# ProPrj___2024-09-27.net
KiCad netlist of a schematic drawn in EasyEDA Pro
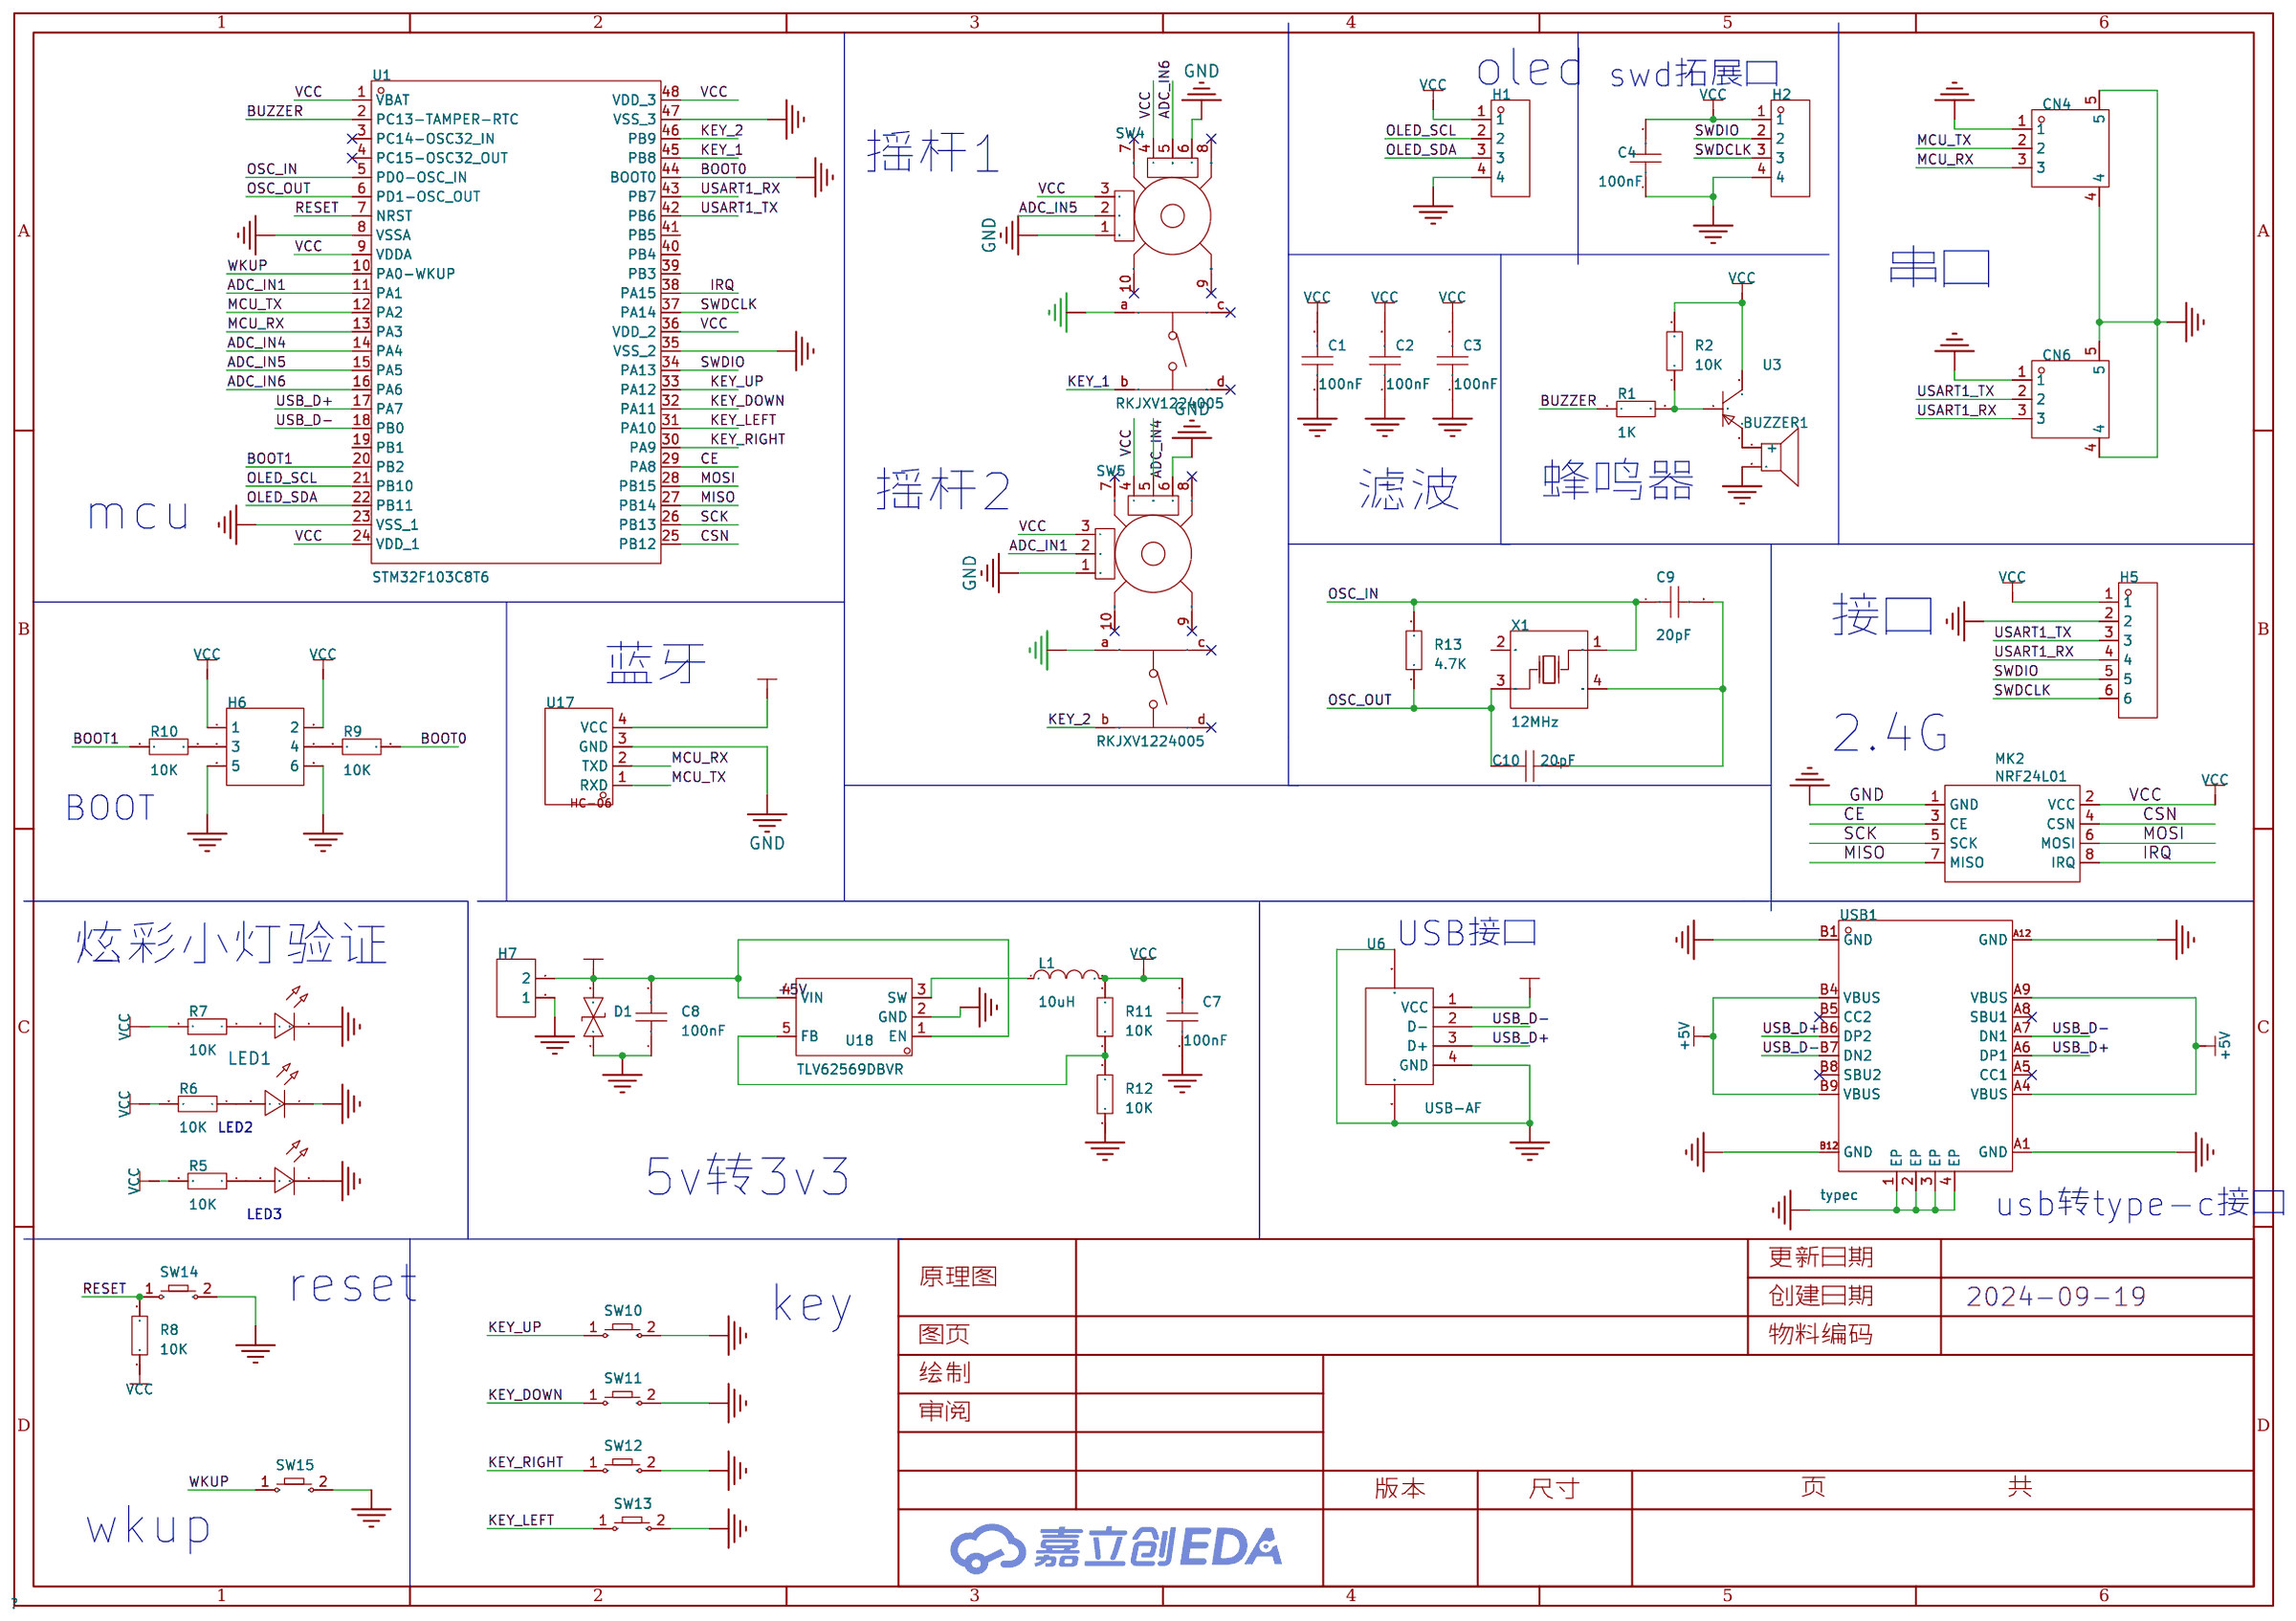
[diagram p0: schematic sheet]

(export (version "E")
  (design (tool "Eeschema 10.0.6"))
  (components
    (comp (ref "BUZZER1")
      (value "buzzer-12X9")
      (footprint "easyedapro:BUZ-TH_BD12.0-P7.60-D0.6-FD")
      (libsource (lib "easyedapro") (part "BUZZER-12X9"))
    )
    (comp (ref "C1")
      (value "100nF")
      (footprint "easyedapro:C0603")
      (libsource (lib "easyedapro") (part "CapAcitance"))
    )
    (comp (ref "C2")
      (value "100nF")
      (footprint "easyedapro:C0603")
      (libsource (lib "easyedapro") (part "CapAcitance"))
    )
    (comp (ref "C3")
      (value "100nF")
      (footprint "easyedapro:C0603")
      (libsource (lib "easyedapro") (part "CapAcitance"))
    )
    (comp (ref "C4")
      (value "100nF")
      (footprint "easyedapro:C0603")
      (libsource (lib "easyedapro") (part "CapAcitance"))
    )
    (comp (ref "C7")
      (value "100nF")
      (footprint "easyedapro:C0603")
      (libsource (lib "easyedapro") (part "CapAcitance"))
    )
    (comp (ref "C8")
      (value "100nF")
      (footprint "easyedapro:C0603")
      (libsource (lib "easyedapro") (part "CapAcitance"))
    )
    (comp (ref "C9")
      (value "20pF")
      (footprint "easyedapro:C0603")
      (libsource (lib "easyedapro") (part "CapAcitance"))
    )
    (comp (ref "C10")
      (value "20pF")
      (footprint "easyedapro:C0603")
      (libsource (lib "easyedapro") (part "CapAcitance"))
    )
    (comp (ref "CN4")
      (value "A1257WV-S-3P")
      (footprint "easyedapro:CONN-SMD_A1257WV-S-3P")
      (description "插针结构:1x3P;间距:1.25mm;安装方式:-;参考系列:GH;总PIN数:3P;排数:1;每排PIN数:3;行距:-;触头材质:黄铜;")
      (fields (field (name "Manufacturer") "CJT(长江连接器)"))
      (libsource (lib "easyedapro") (part "A1257WV-S-3P"))
    )
    (comp (ref "CN6")
      (value "A1257WV-S-3P")
      (footprint "easyedapro:CONN-SMD_A1257WV-S-3P")
      (description "插针结构:1x3P;间距:1.25mm;安装方式:-;参考系列:GH;总PIN数:3P;排数:1;每排PIN数:3;行距:-;触头材质:黄铜;")
      (fields (field (name "Manufacturer") "CJT(长江连接器)"))
      (libsource (lib "easyedapro") (part "A1257WV-S-3P"))
    )
    (comp (ref "D1")
      (value "P6SMB6.8CA/TR13")
      (footprint "easyedapro:SMB_L4.6-W3.6-LS5.3-BI")
      (description "反向截止电压(Vrwm):5.8V;最大钳位电压:10.5V;峰值脉冲电流(Ipp)@10/1000us:58.1A;峰值脉冲功率(Ppp)@10/1000us:600W;击穿电压:6.45V;")
      (fields (field (name "Manufacturer") "Brightking(君耀电子)"))
      (libsource (lib "easyedapro") (part "P6SMB6.8CA-C78395"))
    )
    (comp (ref "H1")
      (value "~")
      (footprint "easyedapro:HDR-TH_4P-P2.54-V-F")
      (libsource (lib "easyedapro") (part "2.54-1*4P母"))
    )
    (comp (ref "H2")
      (value "~")
      (footprint "easyedapro:HDR-TH_4P-P2.54-V-F")
      (libsource (lib "easyedapro") (part "2.54-1*4P母"))
    )
    (comp (ref "H5")
      (value "~")
      (footprint "easyedapro:HDR-TH_6P-P2.54-V-F")
      (libsource (lib "easyedapro") (part "Header-Female-2.54_1x6"))
    )
    (comp (ref "H6")
      (value "~")
      (footprint "easyedapro:HDR-TH_6P-P2.54-V-F-R2-C3-S2.54")
      (libsource (lib "easyedapro") (part "HDR-F-2.54_2x3"))
    )
    (comp (ref "H7")
      (value "~")
      (footprint "easyedapro:HDR-TH_2P-P2.54-V-F")
      (libsource (lib "easyedapro") (part "Header-Female-2.54_1x2"))
    )
    (comp (ref "L1")
      (value "10uH")
      (footprint "easyedapro:L0603")
      (libsource (lib "easyedapro") (part "SDFL1608S100KTF"))
    )
    (comp (ref "LED1")
      (value "~")
      (footprint "easyedapro:LED_0402")
      (libsource (lib "easyedapro") (part "LED_R"))
    )
    (comp (ref "LED2")
      (value "~")
      (footprint "easyedapro:LED_0603")
      (libsource (lib "easyedapro") (part "LED_G"))
    )
    (comp (ref "LED3")
      (value "~")
      (footprint "easyedapro:LED_0603")
      (libsource (lib "easyedapro") (part "LED_B"))
    )
    (comp (ref "MK2")
      (value "NRF24L01")
      (footprint "easyedapro:WIRELM-SMD_NRF24L01")
      (fields
        (field (name "Manufacturer Part") "NRF24L01+功率加强版绑定2.4Gwireless module")
        (field (name "Manufacturer") "Ai-Thinker")
      )
      (libsource (lib "easyedapro") (part "NRF24L01"))
    )
    (comp (ref "R1") (value "1K") (footprint "easyedapro:R0603") (libsource (lib "easyedapro") (part "电阻")))
    (comp (ref "R2") (value "10K") (footprint "easyedapro:R0603") (libsource (lib "easyedapro") (part "电阻")))
    (comp (ref "R5") (value "10K") (footprint "easyedapro:R0603") (libsource (lib "easyedapro") (part "电阻")))
    (comp (ref "R6") (value "10K") (footprint "easyedapro:R0603") (libsource (lib "easyedapro") (part "电阻")))
    (comp (ref "R7") (value "10K") (footprint "easyedapro:R0603") (libsource (lib "easyedapro") (part "电阻")))
    (comp (ref "R8") (value "10K") (footprint "easyedapro:R0603") (libsource (lib "easyedapro") (part "电阻")))
    (comp (ref "R9") (value "10K") (footprint "easyedapro:R0603") (libsource (lib "easyedapro") (part "电阻")))
    (comp (ref "R10") (value "10K") (footprint "easyedapro:R0603") (libsource (lib "easyedapro") (part "电阻")))
    (comp (ref "R11") (value "10K") (footprint "easyedapro:R0603") (libsource (lib "easyedapro") (part "电阻")))
    (comp (ref "R12") (value "10K") (footprint "easyedapro:R0603") (libsource (lib "easyedapro") (part "电阻")))
    (comp (ref "R13")
      (value "4.7K")
      (footprint "easyedapro:R0603")
      (libsource (lib "easyedapro") (part "电阻"))
    )
    (comp (ref "SW4")
      (value "RKJXV1224005")
      (footprint "easyedapro:SW-TH_RKJXV1224005")
      (description "操纵杆复位 中央按动开关 适用于航模玩具遥控器电位器、3D摇杆PS4手柄游戏机、无人机摇杆电位器、工业控制器")
      (fields (field (name "Manufacturer") "ALPSALPINE(阿尔卑斯阿尔派)"))
      (libsource (lib "easyedapro") (part "RKJXV1224005"))
    )
    (comp (ref "SW5")
      (value "RKJXV1224005")
      (footprint "easyedapro:SW-TH_RKJXV1224005")
      (description "操纵杆复位 中央按动开关 适用于航模玩具遥控器电位器、3D摇杆PS4手柄游戏机、无人机摇杆电位器、工业控制器")
      (fields (field (name "Manufacturer") "ALPSALPINE(阿尔卑斯阿尔派)"))
      (libsource (lib "easyedapro") (part "RKJXV1224005"))
    )
    (comp (ref "SW10")
      (value "~")
      (footprint "easyedapro:Key_SMD_3x4x2")
      (libsource (lib "easyedapro") (part "轻触按键x2"))
    )
    (comp (ref "SW11")
      (value "~")
      (footprint "easyedapro:Key_SMD_3x4x2")
      (libsource (lib "easyedapro") (part "轻触按键x2"))
    )
    (comp (ref "SW12")
      (value "~")
      (footprint "easyedapro:Key_SMD_3x4x2")
      (libsource (lib "easyedapro") (part "轻触按键x2"))
    )
    (comp (ref "SW13")
      (value "~")
      (footprint "easyedapro:Key_SMD_3x4x2")
      (libsource (lib "easyedapro") (part "轻触按键x2"))
    )
    (comp (ref "SW14")
      (value "~")
      (footprint "easyedapro:Key_SMD_3x4x2")
      (libsource (lib "easyedapro") (part "轻触按键x2"))
    )
    (comp (ref "SW15")
      (value "~")
      (footprint "easyedapro:Key_SMD_3x4x2")
      (libsource (lib "easyedapro") (part "轻触按键x2"))
    )
    (comp (ref "U1")
      (value "STM32F103C8T6")
      (footprint "easyedapro:LQFP-48_L7.0-W7.0-P0.50-LS9.0-BL")
      (description "CPU内核:ARM-M3;程序存储容量:64KB;RAM总容量:20KB;GPIO端口数量:37;工作电压范围:2V~3.6V;CPU最大主频:72MHz;程序存储器类型:FLASH;")
      (fields (field (name "Manufacturer") "ST(意法半导体)"))
      (libsource (lib "easyedapro") (part "STM32F103C8T6"))
    )
    (comp (ref "U3")
      (value "S9012")
      (footprint "easyedapro:SOT-23-3_L2.9-W1.3-P0.95-LS2.4-BR")
      (fields (field (name "Manufacturer") "MSKSEMI(美森科)"))
      (libsource (lib "easyedapro") (part "S9012_C2914401"))
    )
    (comp (ref "U6")
      (value "USB-AF")
      (footprint "easyedapro:USB-A-TH_USB-302-T")
      (libsource (lib "easyedapro") (part "USB-AF"))
    )
    (comp (ref "U17")
      (value "~")
      (footprint "easyedapro:HC-06")
      (description "蓝牙模块-4P")
      (libsource (lib "easyedapro") (part "HC-06"))
    )
    (comp (ref "U18")
      (value "TLV62569DBVR")
      (footprint "easyedapro:SOT-23-5_L3.0-W1.7-P0.95-LS2.8-BR")
      (description "功能类型:降压型;输出类型:可调;输入电压:2.5V~5.5V;输出电压:600mV~5.5V;输出电流(最大值):2A;")
      (fields (field (name "Manufacturer") "TI(德州仪器)"))
      (libsource (lib "easyedapro") (part "TLV62569DBVR"))
    )
    (comp (ref "USB1")
      (value "typec")
      (footprint "easyedapro:USB-C-SMD_KH-TYPE-C-16P")
      (libsource (lib "easyedapro") (part "TYPEC_C9900016956"))
    )
    (comp (ref "X1")
      (value "12MHz")
      (footprint "easyedapro:OSC-SMD_4P-L3.2-W2.5-BL")
      (description "晶振类型:贴片晶振;频率:12MHz;常温频差:±10ppm;外接负载电容:20pF;频率稳定度(全温):±20ppm;")
      (fields (field (name "Manufacturer Part") "X322512MSB4SI") (field (name "Manufacturer") "YXC(扬兴晶振)"))
      (libsource (lib "easyedapro") (part "X322512MSB4SI"))
    )
  )
  (nets
    (net (code "1") (name "+5V") (class "Default")
      (node (ref "C8") (pin "2") (pinfunction "2_2") (pintype "input"))
      (node (ref "D1") (pin "2") (pinfunction "2_2") (pintype "unspecified"))
      (node (ref "H7") (pin "2") (pinfunction "2_2") (pintype "input"))
      (node (ref "U18") (pin "1") (pinfunction "EN_1") (pintype "unspecified"))
      (node (ref "U18") (pin "4") (pinfunction "VIN_4") (pintype "unspecified"))
      (node (ref "U6") (pin "1") (pinfunction "VCC_1") (pintype "unspecified"))
      (node (ref "USB1") (pin "A4") (pinfunction "VBUS_A4") (pintype "unspecified"))
      (node (ref "USB1") (pin "A9") (pinfunction "VBUS_A9") (pintype "unspecified"))
      (node (ref "USB1") (pin "B4") (pinfunction "VBUS_B4") (pintype "unspecified"))
      (node (ref "USB1") (pin "B9") (pinfunction "VBUS_B9") (pintype "unspecified"))
    )
    (net (code "2") (name "/ADC_IN1") (class "Default")
      (node (ref "SW5") (pin "2") (pinfunction "DTA_2") (pintype "input"))
      (node (ref "U1") (pin "11") (pinfunction "PA1_11") (pintype "unspecified"))
    )
    (net (code "3") (name "/ADC_IN4") (class "Default")
      (node (ref "SW5") (pin "5") (pinfunction "DTA_5") (pintype "input"))
      (node (ref "U1") (pin "14") (pinfunction "PA4_14") (pintype "unspecified"))
    )
    (net (code "4") (name "/ADC_IN5") (class "Default")
      (node (ref "SW4") (pin "2") (pinfunction "DTA_2") (pintype "input"))
      (node (ref "U1") (pin "15") (pinfunction "PA5_15") (pintype "unspecified"))
    )
    (net (code "5") (name "/ADC_IN6") (class "Default")
      (node (ref "SW4") (pin "5") (pinfunction "DTA_5") (pintype "input"))
      (node (ref "U1") (pin "16") (pinfunction "PA6_16") (pintype "unspecified"))
    )
    (net (code "6") (name "/BOOT1") (class "Default")
      (node (ref "R10") (pin "1") (pinfunction "1_1") (pintype "input"))
      (node (ref "U1") (pin "20") (pinfunction "PB2_20") (pintype "unspecified"))
    )
    (net (code "7") (name "/BUZZER") (class "Default")
      (node (ref "R1") (pin "1") (pinfunction "1_1") (pintype "input"))
      (node (ref "U1") (pin "2") (pinfunction "PC13-TAMPER-RTC_2") (pintype "unspecified"))
    )
    (net (code "8") (name "/CE") (class "Default")
      (node (ref "MK2") (pin "3") (pinfunction "CE_3") (pintype "unspecified"))
      (node (ref "U1") (pin "29") (pinfunction "PA8_29") (pintype "unspecified"))
    )
    (net (code "9") (name "/CSN") (class "Default")
      (node (ref "MK2") (pin "4") (pinfunction "CSN_4") (pintype "unspecified"))
      (node (ref "U1") (pin "25") (pinfunction "PB12_25") (pintype "unspecified"))
    )
    (net (code "10") (name "/IRQ") (class "Default")
      (node (ref "MK2") (pin "8") (pinfunction "IRQ_8") (pintype "unspecified"))
      (node (ref "U1") (pin "38") (pinfunction "PA15_38") (pintype "unspecified"))
    )
    (net (code "11") (name "/KEY_1") (class "Default")
      (node (ref "SW4") (pin "b") (pinfunction "b_b") (pintype "input"))
      (node (ref "U1") (pin "45") (pinfunction "PB8_45") (pintype "unspecified"))
    )
    (net (code "12") (name "/KEY_2") (class "Default")
      (node (ref "SW5") (pin "b") (pinfunction "b_b") (pintype "input"))
      (node (ref "U1") (pin "46") (pinfunction "PB9_46") (pintype "unspecified"))
    )
    (net (code "13") (name "/KEY_DOWN") (class "Default")
      (node (ref "SW11") (pin "1") (pinfunction "1_1") (pintype "input"))
      (node (ref "U1") (pin "32") (pinfunction "PA11_32") (pintype "unspecified"))
    )
    (net (code "14") (name "/KEY_LEFT") (class "Default")
      (node (ref "SW13") (pin "1") (pinfunction "1_1") (pintype "input"))
      (node (ref "U1") (pin "31") (pinfunction "PA10_31") (pintype "unspecified"))
    )
    (net (code "15") (name "/KEY_RIGHT") (class "Default")
      (node (ref "SW12") (pin "1") (pinfunction "1_1") (pintype "input"))
      (node (ref "U1") (pin "30") (pinfunction "PA9_30") (pintype "unspecified"))
    )
    (net (code "16") (name "/KEY_UP") (class "Default")
      (node (ref "SW10") (pin "1") (pinfunction "1_1") (pintype "input"))
      (node (ref "U1") (pin "33") (pinfunction "PA12_33") (pintype "unspecified"))
    )
    (net (code "17") (name "/MCU_RX") (class "Default")
      (node (ref "CN4") (pin "3") (pinfunction "3_3") (pintype "unspecified"))
      (node (ref "U1") (pin "13") (pinfunction "PA3_13") (pintype "unspecified"))
      (node (ref "U17") (pin "2") (pinfunction "TXD_2") (pintype "input"))
    )
    (net (code "18") (name "/MCU_TX") (class "Default")
      (node (ref "CN4") (pin "2") (pinfunction "2_2") (pintype "unspecified"))
      (node (ref "U1") (pin "12") (pinfunction "PA2_12") (pintype "unspecified"))
      (node (ref "U17") (pin "1") (pinfunction "RXD_1") (pintype "input"))
    )
    (net (code "19") (name "/MISO") (class "Default")
      (node (ref "MK2") (pin "7") (pinfunction "MISO_7") (pintype "unspecified"))
      (node (ref "U1") (pin "27") (pinfunction "PB14_27") (pintype "unspecified"))
    )
    (net (code "20") (name "/MOSI") (class "Default")
      (node (ref "MK2") (pin "6") (pinfunction "MOSI_6") (pintype "unspecified"))
      (node (ref "U1") (pin "28") (pinfunction "PB15_28") (pintype "unspecified"))
    )
    (net (code "21") (name "/OLED_SCL") (class "Default")
      (node (ref "H1") (pin "2") (pinfunction "2_2") (pintype "unspecified"))
      (node (ref "U1") (pin "21") (pinfunction "PB10_21") (pintype "unspecified"))
    )
    (net (code "22") (name "/OLED_SDA") (class "Default")
      (node (ref "H1") (pin "3") (pinfunction "3_3") (pintype "unspecified"))
      (node (ref "U1") (pin "22") (pinfunction "PB11_22") (pintype "unspecified"))
    )
    (net (code "23") (name "/OSC_IN") (class "Default")
      (node (ref "C9") (pin "1") (pinfunction "1_1") (pintype "input"))
      (node (ref "R13") (pin "2") (pinfunction "2_2") (pintype "input"))
      (node (ref "U1") (pin "5") (pinfunction "PD0-OSC_IN_5") (pintype "unspecified"))
      (node (ref "X1") (pin "1") (pinfunction "OSC1_1") (pintype "unspecified"))
    )
    (net (code "24") (name "/OSC_OUT") (class "Default")
      (node (ref "C10") (pin "1") (pinfunction "1_1") (pintype "input"))
      (node (ref "R13") (pin "1") (pinfunction "1_1") (pintype "input"))
      (node (ref "U1") (pin "6") (pinfunction "PD1-OSC_OUT_6") (pintype "unspecified"))
      (node (ref "X1") (pin "3") (pinfunction "OSC2_3") (pintype "unspecified"))
    )
    (net (code "25") (name "/RESET") (class "Default")
      (node (ref "R8") (pin "2") (pinfunction "2_2") (pintype "input"))
      (node (ref "SW14") (pin "1") (pinfunction "1_1") (pintype "input"))
      (node (ref "U1") (pin "7") (pinfunction "NRST_7") (pintype "unspecified"))
    )
    (net (code "26") (name "/SCK") (class "Default")
      (node (ref "MK2") (pin "5") (pinfunction "SCK_5") (pintype "unspecified"))
      (node (ref "U1") (pin "26") (pinfunction "PB13_26") (pintype "unspecified"))
    )
    (net (code "27") (name "/SWDCLK") (class "Default")
      (node (ref "H2") (pin "3") (pinfunction "3_3") (pintype "unspecified"))
      (node (ref "H5") (pin "6") (pinfunction "6_6") (pintype "unspecified"))
      (node (ref "U1") (pin "37") (pinfunction "PA14_37") (pintype "unspecified"))
    )
    (net (code "28") (name "/SWDIO") (class "Default")
      (node (ref "H2") (pin "2") (pinfunction "2_2") (pintype "unspecified"))
      (node (ref "H5") (pin "5") (pinfunction "5_5") (pintype "unspecified"))
      (node (ref "U1") (pin "34") (pinfunction "PA13_34") (pintype "unspecified"))
    )
    (net (code "29") (name "/USART1_RX") (class "Default")
      (node (ref "CN6") (pin "3") (pinfunction "3_3") (pintype "unspecified"))
      (node (ref "H5") (pin "4") (pinfunction "4_4") (pintype "unspecified"))
      (node (ref "U1") (pin "43") (pinfunction "PB7_43") (pintype "unspecified"))
    )
    (net (code "30") (name "/USART1_TX") (class "Default")
      (node (ref "CN6") (pin "2") (pinfunction "2_2") (pintype "unspecified"))
      (node (ref "H5") (pin "3") (pinfunction "3_3") (pintype "unspecified"))
      (node (ref "U1") (pin "42") (pinfunction "PB6_42") (pintype "unspecified"))
    )
    (net (code "31") (name "/USB_D+") (class "Default")
      (node (ref "U1") (pin "17") (pinfunction "PA7_17") (pintype "unspecified"))
      (node (ref "U6") (pin "3") (pinfunction "D+_3") (pintype "unspecified"))
      (node (ref "USB1") (pin "A6") (pinfunction "DP1_A6") (pintype "unspecified"))
      (node (ref "USB1") (pin "B6") (pinfunction "DP2_B6") (pintype "unspecified"))
    )
    (net (code "32") (name "/USB_D-") (class "Default")
      (node (ref "U1") (pin "18") (pinfunction "PB0_18") (pintype "unspecified"))
      (node (ref "U6") (pin "2") (pinfunction "D-_2") (pintype "unspecified"))
      (node (ref "USB1") (pin "A7") (pinfunction "DN1_A7") (pintype "unspecified"))
      (node (ref "USB1") (pin "B7") (pinfunction "DN2_B7") (pintype "unspecified"))
    )
    (net (code "33") (name "/WKUP") (class "Default")
      (node (ref "SW15") (pin "1") (pinfunction "1_1") (pintype "input"))
      (node (ref "U1") (pin "10") (pinfunction "PA0-WKUP_10") (pintype "unspecified"))
    )
    (net (code "34") (name "BOOT0") (class "Default")
      (node (ref "R9") (pin "2") (pinfunction "2_2") (pintype "input"))
      (node (ref "U1") (pin "44") (pinfunction "BOOT0_44") (pintype "unspecified"))
    )
    (net (code "35") (name "GND") (class "Default")
      (node (ref "BUZZER1") (pin "2") (pinfunction "2_2") (pintype "unspecified"))
      (node (ref "C1") (pin "1") (pinfunction "1_1") (pintype "input"))
      (node (ref "C2") (pin "1") (pinfunction "1_1") (pintype "input"))
      (node (ref "C3") (pin "1") (pinfunction "1_1") (pintype "input"))
      (node (ref "C4") (pin "1") (pinfunction "1_1") (pintype "input"))
      (node (ref "C7") (pin "1") (pinfunction "1_1") (pintype "input"))
      (node (ref "C8") (pin "1") (pinfunction "1_1") (pintype "input"))
      (node (ref "CN4") (pin "1") (pinfunction "1_1") (pintype "unspecified"))
      (node (ref "CN4") (pin "4") (pinfunction "4_4") (pintype "unspecified"))
      (node (ref "CN4") (pin "5") (pinfunction "5_5") (pintype "unspecified"))
      (node (ref "CN6") (pin "1") (pinfunction "1_1") (pintype "unspecified"))
      (node (ref "CN6") (pin "4") (pinfunction "4_4") (pintype "unspecified"))
      (node (ref "CN6") (pin "5") (pinfunction "5_5") (pintype "unspecified"))
      (node (ref "D1") (pin "1") (pinfunction "1_1") (pintype "unspecified"))
      (node (ref "H1") (pin "4") (pinfunction "4_4") (pintype "unspecified"))
      (node (ref "H2") (pin "4") (pinfunction "4_4") (pintype "unspecified"))
      (node (ref "H5") (pin "2") (pinfunction "2_2") (pintype "unspecified"))
      (node (ref "H6") (pin "5") (pinfunction "5_5") (pintype "input"))
      (node (ref "H6") (pin "6") (pinfunction "6_6") (pintype "input"))
      (node (ref "H7") (pin "1") (pinfunction "1_1") (pintype "input"))
      (node (ref "LED1") (pin "1") (pinfunction "C_1") (pintype "input"))
      (node (ref "LED2") (pin "1") (pinfunction "C_1") (pintype "input"))
      (node (ref "LED3") (pin "1") (pinfunction "C_1") (pintype "input"))
      (node (ref "MK2") (pin "1") (pinfunction "GND_1") (pintype "unspecified"))
      (node (ref "R12") (pin "1") (pinfunction "1_1") (pintype "input"))
      (node (ref "SW10") (pin "2") (pinfunction "2_2") (pintype "input"))
      (node (ref "SW11") (pin "2") (pinfunction "2_2") (pintype "input"))
      (node (ref "SW12") (pin "2") (pinfunction "2_2") (pintype "input"))
      (node (ref "SW13") (pin "2") (pinfunction "2_2") (pintype "input"))
      (node (ref "SW14") (pin "2") (pinfunction "2_2") (pintype "input"))
      (node (ref "SW15") (pin "2") (pinfunction "2_2") (pintype "input"))
      (node (ref "SW4") (pin "1") (pinfunction "B_1") (pintype "input"))
      (node (ref "SW4") (pin "6") (pinfunction "B_6") (pintype "input"))
      (node (ref "SW4") (pin "a") (pinfunction "a_a") (pintype "input"))
      (node (ref "SW5") (pin "1") (pinfunction "B_1") (pintype "input"))
      (node (ref "SW5") (pin "6") (pinfunction "B_6") (pintype "input"))
      (node (ref "SW5") (pin "a") (pinfunction "a_a") (pintype "input"))
      (node (ref "U1") (pin "23") (pinfunction "VSS_1_23") (pintype "unspecified"))
      (node (ref "U1") (pin "35") (pinfunction "VSS_2_35") (pintype "unspecified"))
      (node (ref "U1") (pin "47") (pinfunction "VSS_3_47") (pintype "unspecified"))
      (node (ref "U1") (pin "8") (pinfunction "VSSA_8") (pintype "unspecified"))
      (node (ref "U17") (pin "3") (pinfunction "GND_3") (pintype "input"))
      (node (ref "U18") (pin "2") (pinfunction "GND_2") (pintype "unspecified"))
      (node (ref "U6") (pin "4") (pinfunction "GND_4") (pintype "unspecified"))
      (node (ref "U6") (pin "5") (pinfunction "5_5") (pintype "unspecified"))
      (node (ref "U6") (pin "6") (pinfunction "6_6") (pintype "unspecified"))
      (node (ref "USB1") (pin "1") (pinfunction "EP_1") (pintype "unspecified"))
      (node (ref "USB1") (pin "2") (pinfunction "EP_2") (pintype "unspecified"))
      (node (ref "USB1") (pin "3") (pinfunction "EP_3") (pintype "unspecified"))
      (node (ref "USB1") (pin "4") (pinfunction "EP_4") (pintype "unspecified"))
      (node (ref "USB1") (pin "A1") (pinfunction "GND_A1") (pintype "unspecified"))
      (node (ref "USB1") (pin "A12") (pinfunction "GND_A12") (pintype "unspecified"))
      (node (ref "USB1") (pin "B1") (pinfunction "GND_B1") (pintype "unspecified"))
      (node (ref "USB1") (pin "B12") (pinfunction "GND_B12") (pintype "unspecified"))
    )
    (net (code "36") (name "Net-(BUZZER1-+)") (class "Default")
      (node (ref "BUZZER1") (pin "1") (pinfunction "+_1") (pintype "unspecified"))
      (node (ref "U3") (pin "2") (pinfunction "E_2") (pintype "input"))
    )
    (net (code "37") (name "Net-(C10-Pad2)") (class "Default")
      (node (ref "C10") (pin "2") (pinfunction "2_2") (pintype "input"))
      (node (ref "C9") (pin "2") (pinfunction "2_2") (pintype "input"))
      (node (ref "X1") (pin "4") (pinfunction "GND_4") (pintype "unspecified"))
    )
    (net (code "38") (name "Net-(H6-Pad3)") (class "Default")
      (node (ref "H6") (pin "3") (pinfunction "3_3") (pintype "input"))
      (node (ref "R10") (pin "2") (pinfunction "2_2") (pintype "input"))
    )
    (net (code "39") (name "Net-(H6-Pad4)") (class "Default")
      (node (ref "H6") (pin "4") (pinfunction "4_4") (pintype "input"))
      (node (ref "R9") (pin "1") (pinfunction "1_1") (pintype "input"))
    )
    (net (code "40") (name "Net-(LED1-A)") (class "Default")
      (node (ref "LED1") (pin "2") (pinfunction "A_2") (pintype "input"))
      (node (ref "R7") (pin "1") (pinfunction "1_1") (pintype "input"))
    )
    (net (code "41") (name "Net-(LED2-A)") (class "Default")
      (node (ref "LED2") (pin "2") (pinfunction "A_2") (pintype "input"))
      (node (ref "R6") (pin "1") (pinfunction "1_1") (pintype "input"))
    )
    (net (code "42") (name "Net-(LED3-A)") (class "Default")
      (node (ref "LED3") (pin "2") (pinfunction "A_2") (pintype "input"))
      (node (ref "R5") (pin "1") (pinfunction "1_1") (pintype "input"))
    )
    (net (code "43") (name "Net-(U3-B)") (class "Default")
      (node (ref "R1") (pin "2") (pinfunction "2_2") (pintype "input"))
      (node (ref "R2") (pin "1") (pinfunction "1_1") (pintype "input"))
      (node (ref "U3") (pin "1") (pinfunction "B_1") (pintype "input"))
    )
    (net (code "44") (name "Net-(U18-FB)") (class "Default")
      (node (ref "R11") (pin "1") (pinfunction "1_1") (pintype "input"))
      (node (ref "R12") (pin "2") (pinfunction "2_2") (pintype "input"))
      (node (ref "U18") (pin "5") (pinfunction "FB_5") (pintype "unspecified"))
    )
    (net (code "45") (name "Net-(U18-SW)") (class "Default")
      (node (ref "L1") (pin "1") (pinfunction "1_1") (pintype "unspecified"))
      (node (ref "U18") (pin "3") (pinfunction "SW_3") (pintype "unspecified"))
    )
    (net (code "46") (name "VCC") (class "Default")
      (node (ref "C1") (pin "2") (pinfunction "2_2") (pintype "input"))
      (node (ref "C2") (pin "2") (pinfunction "2_2") (pintype "input"))
      (node (ref "C3") (pin "2") (pinfunction "2_2") (pintype "input"))
      (node (ref "C4") (pin "2") (pinfunction "2_2") (pintype "input"))
      (node (ref "C7") (pin "2") (pinfunction "2_2") (pintype "input"))
      (node (ref "H1") (pin "1") (pinfunction "1_1") (pintype "unspecified"))
      (node (ref "H2") (pin "1") (pinfunction "1_1") (pintype "unspecified"))
      (node (ref "H5") (pin "1") (pinfunction "1_1") (pintype "unspecified"))
      (node (ref "H6") (pin "1") (pinfunction "1_1") (pintype "input"))
      (node (ref "H6") (pin "2") (pinfunction "2_2") (pintype "input"))
      (node (ref "L1") (pin "2") (pinfunction "2_2") (pintype "unspecified"))
      (node (ref "MK2") (pin "2") (pinfunction "VCC_2") (pintype "unspecified"))
      (node (ref "R11") (pin "2") (pinfunction "2_2") (pintype "input"))
      (node (ref "R2") (pin "2") (pinfunction "2_2") (pintype "input"))
      (node (ref "R5") (pin "2") (pinfunction "2_2") (pintype "input"))
      (node (ref "R6") (pin "2") (pinfunction "2_2") (pintype "input"))
      (node (ref "R7") (pin "2") (pinfunction "2_2") (pintype "input"))
      (node (ref "R8") (pin "1") (pinfunction "1_1") (pintype "input"))
      (node (ref "SW4") (pin "3") (pinfunction "A_3") (pintype "input"))
      (node (ref "SW4") (pin "4") (pinfunction "A_4") (pintype "input"))
      (node (ref "SW5") (pin "3") (pinfunction "A_3") (pintype "input"))
      (node (ref "SW5") (pin "4") (pinfunction "A_4") (pintype "input"))
      (node (ref "U1") (pin "1") (pinfunction "VBAT_1") (pintype "unspecified"))
      (node (ref "U1") (pin "24") (pinfunction "VDD_1_24") (pintype "unspecified"))
      (node (ref "U1") (pin "36") (pinfunction "VDD_2_36") (pintype "unspecified"))
      (node (ref "U1") (pin "48") (pinfunction "VDD_3_48") (pintype "unspecified"))
      (node (ref "U1") (pin "9") (pinfunction "VDDA_9") (pintype "unspecified"))
      (node (ref "U17") (pin "4") (pinfunction "VCC_4") (pintype "input"))
      (node (ref "U3") (pin "3") (pinfunction "C_3") (pintype "input"))
    )
    (net (code "47") (name "unconnected-(SW4-GND-Pad7)") (class "Default")
      (node (ref "SW4") (pin "7") (pinfunction "GND_7") (pintype "input+no_connect"))
    )
    (net (code "48") (name "unconnected-(SW4-GND-Pad8)") (class "Default")
      (node (ref "SW4") (pin "8") (pinfunction "GND_8") (pintype "input+no_connect"))
    )
    (net (code "49") (name "unconnected-(SW4-GND-Pad9)") (class "Default")
      (node (ref "SW4") (pin "9") (pinfunction "GND_9") (pintype "input+no_connect"))
    )
    (net (code "50") (name "unconnected-(SW4-GND-Pad10)") (class "Default")
      (node (ref "SW4") (pin "10") (pinfunction "GND_10") (pintype "input+no_connect"))
    )
    (net (code "51") (name "unconnected-(SW4-Padc)") (class "Default")
      (node (ref "SW4") (pin "c") (pinfunction "c_c") (pintype "input+no_connect"))
    )
    (net (code "52") (name "unconnected-(SW4-Padd)") (class "Default")
      (node (ref "SW4") (pin "d") (pinfunction "d_d") (pintype "input+no_connect"))
    )
    (net (code "53") (name "unconnected-(SW5-GND-Pad7)") (class "Default")
      (node (ref "SW5") (pin "7") (pinfunction "GND_7") (pintype "input+no_connect"))
    )
    (net (code "54") (name "unconnected-(SW5-GND-Pad8)") (class "Default")
      (node (ref "SW5") (pin "8") (pinfunction "GND_8") (pintype "input+no_connect"))
    )
    (net (code "55") (name "unconnected-(SW5-GND-Pad9)") (class "Default")
      (node (ref "SW5") (pin "9") (pinfunction "GND_9") (pintype "input+no_connect"))
    )
    (net (code "56") (name "unconnected-(SW5-GND-Pad10)") (class "Default")
      (node (ref "SW5") (pin "10") (pinfunction "GND_10") (pintype "input+no_connect"))
    )
    (net (code "57") (name "unconnected-(SW5-Padc)") (class "Default")
      (node (ref "SW5") (pin "c") (pinfunction "c_c") (pintype "input+no_connect"))
    )
    (net (code "58") (name "unconnected-(SW5-Padd)") (class "Default")
      (node (ref "SW5") (pin "d") (pinfunction "d_d") (pintype "input+no_connect"))
    )
    (net (code "59") (name "unconnected-(U1-PB1-Pad19)") (class "Default")
      (node (ref "U1") (pin "19") (pinfunction "PB1_19") (pintype "unspecified"))
    )
    (net (code "60") (name "unconnected-(U1-PB3-Pad39)") (class "Default")
      (node (ref "U1") (pin "39") (pinfunction "PB3_39") (pintype "unspecified"))
    )
    (net (code "61") (name "unconnected-(U1-PB4-Pad40)") (class "Default")
      (node (ref "U1") (pin "40") (pinfunction "PB4_40") (pintype "unspecified"))
    )
    (net (code "62") (name "unconnected-(U1-PB5-Pad41)") (class "Default")
      (node (ref "U1") (pin "41") (pinfunction "PB5_41") (pintype "unspecified"))
    )
    (net (code "63") (name "unconnected-(U1-PC14-OSC32_IN-Pad3)") (class "Default")
      (node (ref "U1") (pin "3") (pinfunction "PC14-OSC32_IN_3") (pintype "unspecified+no_connect"))
    )
    (net (code "64") (name "unconnected-(U1-PC15-OSC32_OUT-Pad4)") (class "Default")
      (node (ref "U1") (pin "4") (pinfunction "PC15-OSC32_OUT_4") (pintype "unspecified+no_connect"))
    )
    (net (code "65") (name "unconnected-(USB1-CC1-PadA5)") (class "Default")
      (node (ref "USB1") (pin "A5") (pinfunction "CC1_A5") (pintype "unspecified+no_connect"))
    )
    (net (code "66") (name "unconnected-(USB1-CC2-PadB5)") (class "Default")
      (node (ref "USB1") (pin "B5") (pinfunction "CC2_B5") (pintype "unspecified+no_connect"))
    )
    (net (code "67") (name "unconnected-(USB1-SBU1-PadA8)") (class "Default")
      (node (ref "USB1") (pin "A8") (pinfunction "SBU1_A8") (pintype "unspecified+no_connect"))
    )
    (net (code "68") (name "unconnected-(USB1-SBU2-PadB8)") (class "Default")
      (node (ref "USB1") (pin "B8") (pinfunction "SBU2_B8") (pintype "unspecified+no_connect"))
    )
    (net (code "69") (name "unconnected-(X1-GND-Pad2)") (class "Default")
      (node (ref "X1") (pin "2") (pinfunction "GND_2") (pintype "unspecified"))
    )
  )
)
